# switch-pth-16mm-mk-1_0.net
KiCad netlist of a schematic drawn in EAGLE
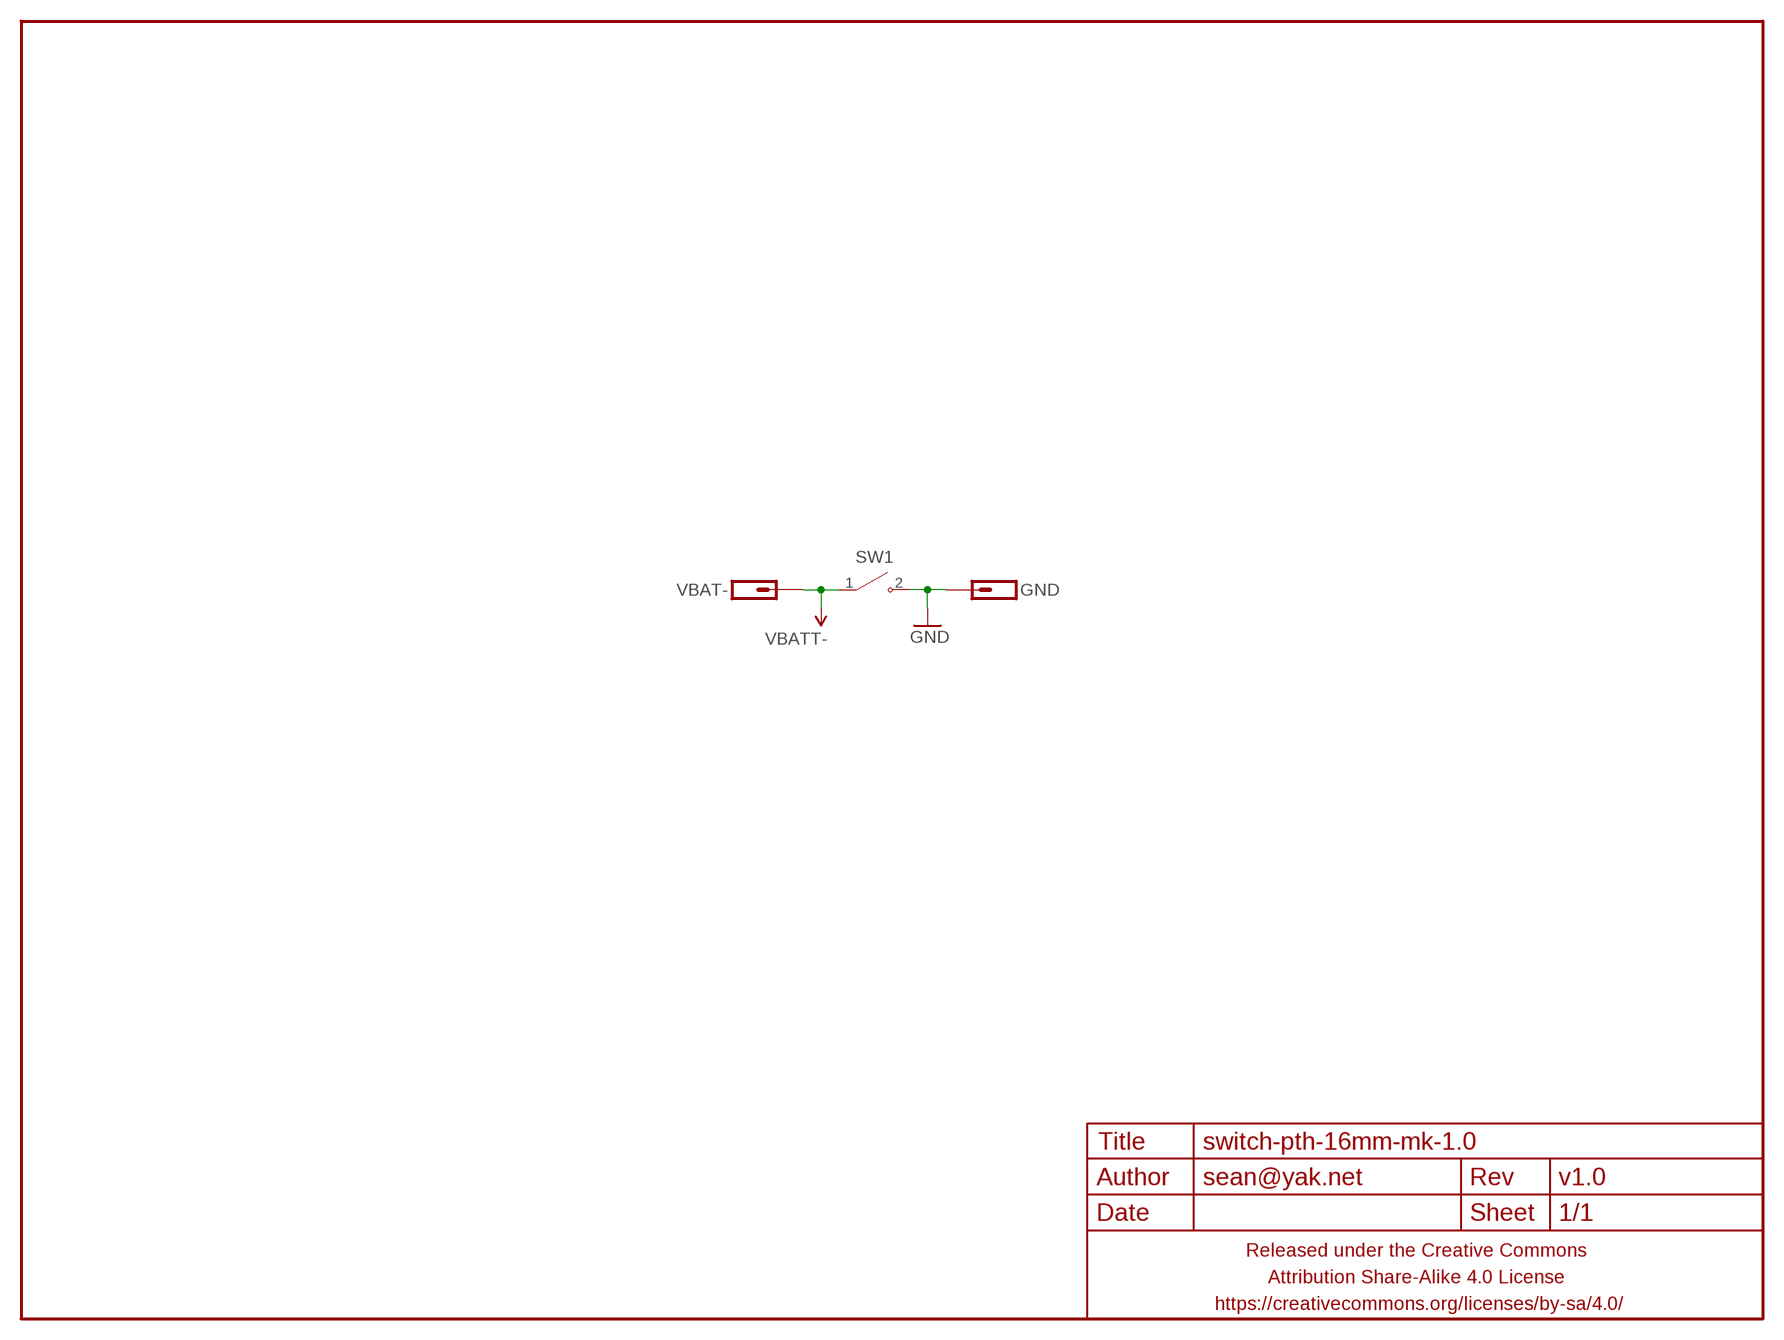
[diagram p0: schematic, sheet 1]

(export (version "E")
  (design (tool "Eeschema 10.0.6"))
  (components
    (comp (ref "FRAME1")
      (value "FRAME-LETTERNO_PACKAGE")
      (footprint "eagle-import:DUMMY")
      (fields (field (name "DESIGNER") "sean@yak.net") (field (name "VERSION") "v1.0"))
      (libsource (lib "eagle-import") (part "FRAME-LETTERNO_PACKAGE"))
    )
    (comp (ref "GND")
      (value "M01NOT-A-VIA-NOPE")
      (footprint "eagle-import:1X01_NOSILK_NOSTOP")
      (libsource (lib "eagle-import") (part "M01NOT-A-VIA-NOPE"))
    )
    (comp (ref "SW1")
      (value "SWITCH-SPSTOMTEN-1288-PTH-NARROWER")
      (footprint "eagle-import:OMTEN-1288-PTH-NARROWER")
      (libsource (lib "eagle-import") (part "SWITCH-SPSTOMTEN-1288-PTH-NARROWER"))
    )
    (comp (ref "VBAT-")
      (value "M01PTH-1.2MM-NS")
      (footprint "eagle-import:1X01-1.2MM-NS")
      (libsource (lib "eagle-import") (part "M01PTH-1.2MM-NS"))
    )
  )
  (nets
    (net (code "1") (name "GND") (class "Default")
      (node (ref "GND") (pin "P$1") (pinfunction "1_P$1") (pintype "passive"))
      (node (ref "SW1") (pin "2") (pinfunction "NO_2") (pintype "bidirectional"))
    )
    (net (code "2") (name "VBATT-") (class "Default")
      (node (ref "SW1") (pin "1") (pinfunction "COM_1") (pintype "bidirectional"))
      (node (ref "VBAT-") (pin "P$1") (pinfunction "1_P$1") (pintype "passive"))
    )
  )
)
